# DLPG_ctrl_v3.net
KiCad netlist of a schematic drawn in EAGLE
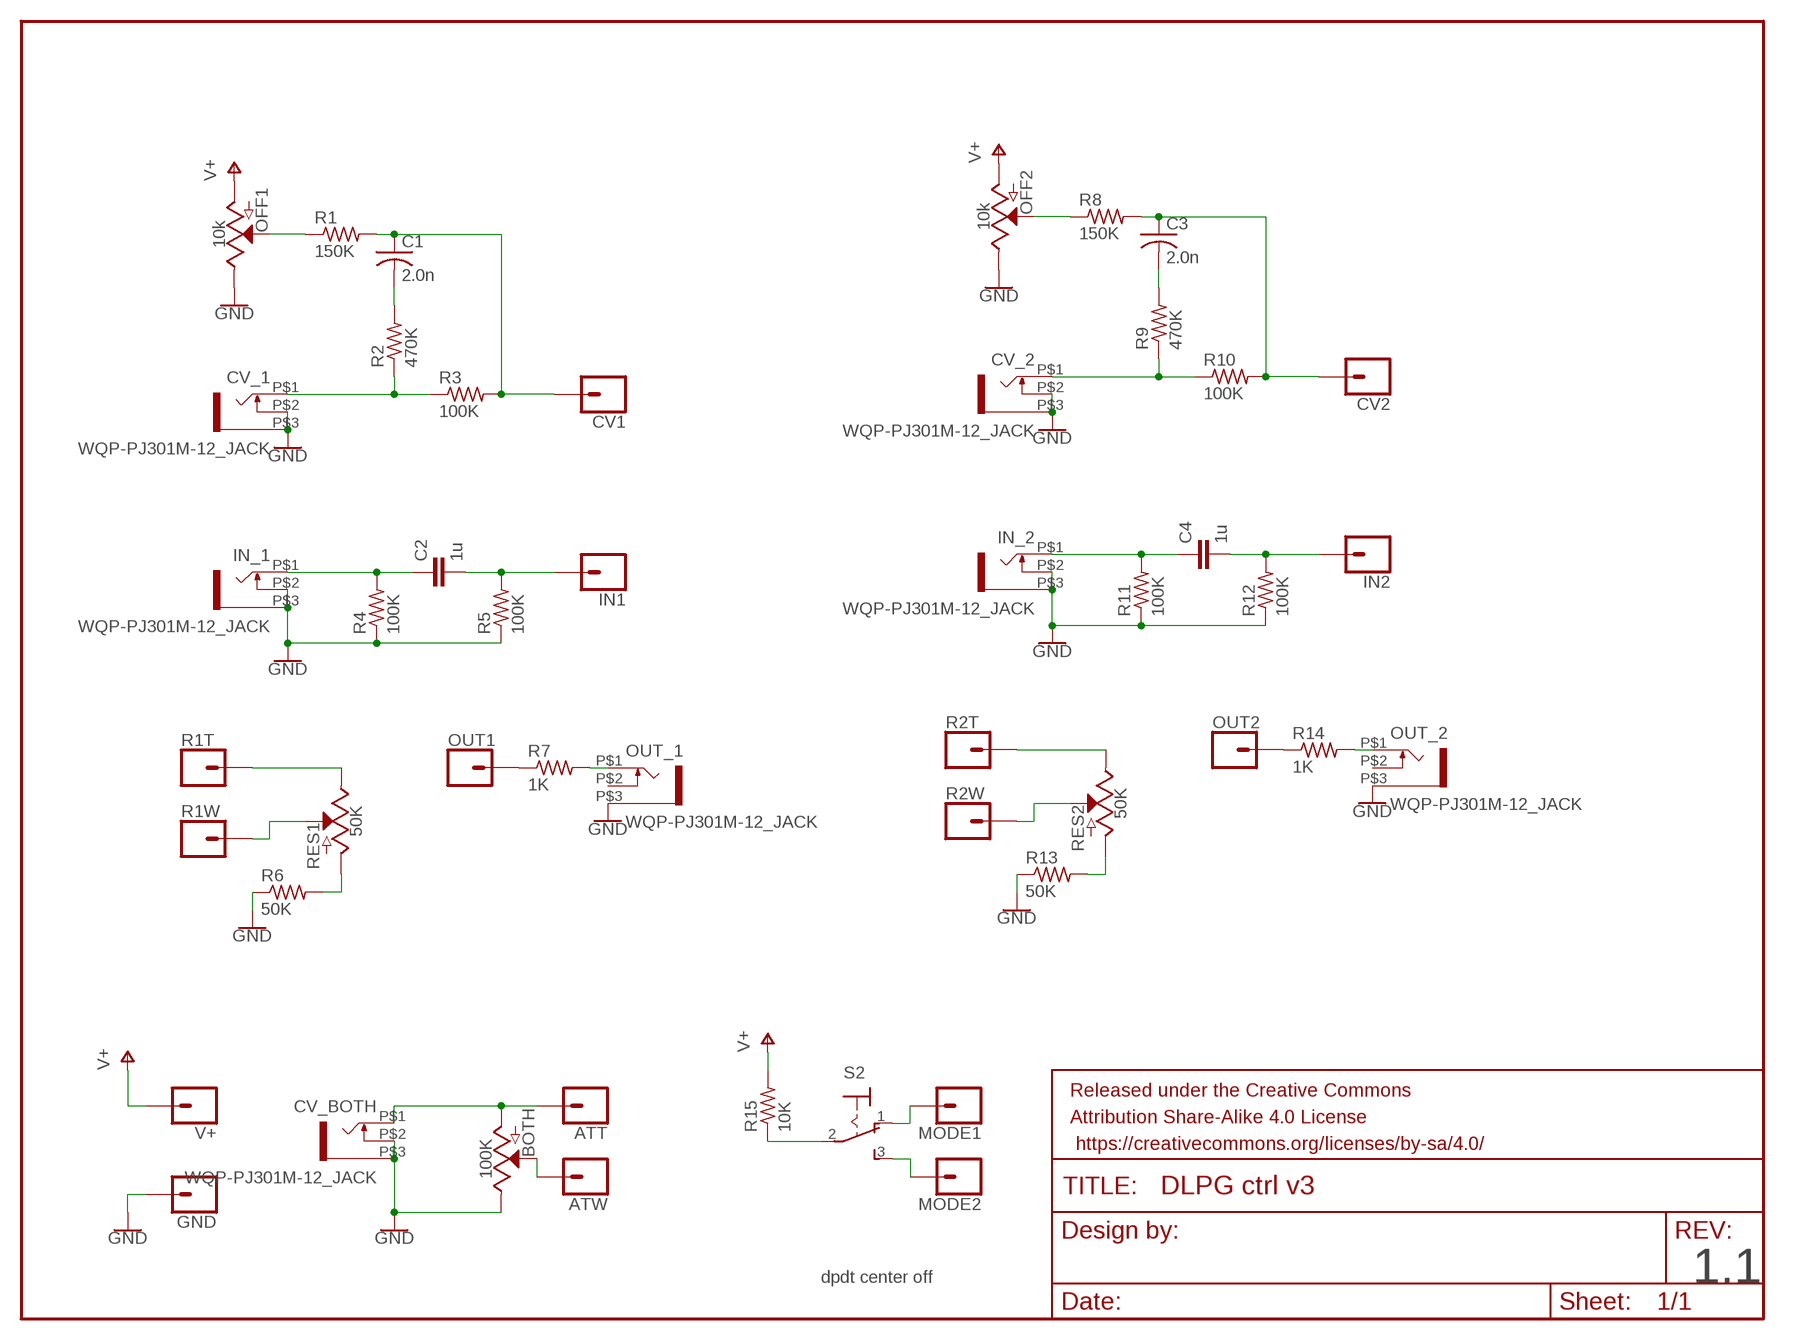
[diagram p0: schematic, sheet 1]

(export (version "E")
  (design (tool "Eeschema 10.0.6"))
  (components
    (comp (ref "ATT")
      (value "CONN_01")
      (footprint "eagle-import:1X01")
      (libsource (lib "eagle-import") (part "CONN_01"))
    )
    (comp (ref "ATW")
      (value "CONN_01")
      (footprint "eagle-import:1X01")
      (libsource (lib "eagle-import") (part "CONN_01"))
    )
    (comp (ref "BOTH")
      (value "100K")
      (footprint "eagle-import:POT-PTH-ALPS")
      (libsource (lib "eagle-import") (part "POTENTIOMETER-PTH-9MM-1/20W-20%"))
    )
    (comp (ref "C1")
      (value "2.0n")
      (footprint "eagle-import:C0805K")
      (libsource (lib "eagle-import") (part "C-USC0805K"))
    )
    (comp (ref "C2")
      (value "1u")
      (footprint "eagle-import:C2220K")
      (libsource (lib "eagle-import") (part "C-EUC2220K"))
    )
    (comp (ref "C3")
      (value "2.0n")
      (footprint "eagle-import:C0805K")
      (libsource (lib "eagle-import") (part "C-USC0805K"))
    )
    (comp (ref "C4")
      (value "1u")
      (footprint "eagle-import:C2220K")
      (libsource (lib "eagle-import") (part "C-EUC2220K"))
    )
    (comp (ref "CV1")
      (value "CONN_01")
      (footprint "eagle-import:1X01")
      (libsource (lib "eagle-import") (part "CONN_01"))
    )
    (comp (ref "CV2")
      (value "CONN_01")
      (footprint "eagle-import:1X01")
      (libsource (lib "eagle-import") (part "CONN_01"))
    )
    (comp (ref "CV_1")
      (value "WQP-PJ301M-12_JACK")
      (footprint "eagle-import:WQP-PJ301M-12_JACK")
      (libsource (lib "eagle-import") (part "WQP-PJ301M-12_JACK"))
    )
    (comp (ref "CV_2")
      (value "WQP-PJ301M-12_JACK")
      (footprint "eagle-import:WQP-PJ301M-12_JACK")
      (libsource (lib "eagle-import") (part "WQP-PJ301M-12_JACK"))
    )
    (comp (ref "CV_BOTH")
      (value "WQP-PJ301M-12_JACK")
      (footprint "eagle-import:WQP-PJ301M-12_JACK")
      (libsource (lib "eagle-import") (part "WQP-PJ301M-12_JACK"))
    )
    (comp (ref "FRAME1")
      (value "FRAME-LETTERNO_PACKAGE")
      (footprint "eagle-import:DUMMY")
      (fields (field (name "DESIGNER") "Nobody"))
      (libsource (lib "eagle-import") (part "FRAME-LETTERNO_PACKAGE"))
    )
    (comp (ref "GND")
      (value "CONN_01")
      (footprint "eagle-import:1X01")
      (libsource (lib "eagle-import") (part "CONN_01"))
    )
    (comp (ref "IN1")
      (value "CONN_01")
      (footprint "eagle-import:1X01")
      (libsource (lib "eagle-import") (part "CONN_01"))
    )
    (comp (ref "IN2")
      (value "CONN_01")
      (footprint "eagle-import:1X01")
      (libsource (lib "eagle-import") (part "CONN_01"))
    )
    (comp (ref "IN_1")
      (value "WQP-PJ301M-12_JACK")
      (footprint "eagle-import:WQP-PJ301M-12_JACK")
      (libsource (lib "eagle-import") (part "WQP-PJ301M-12_JACK"))
    )
    (comp (ref "IN_2")
      (value "WQP-PJ301M-12_JACK")
      (footprint "eagle-import:WQP-PJ301M-12_JACK")
      (libsource (lib "eagle-import") (part "WQP-PJ301M-12_JACK"))
    )
    (comp (ref "MODE1")
      (value "CONN_01")
      (footprint "eagle-import:1X01")
      (libsource (lib "eagle-import") (part "CONN_01"))
    )
    (comp (ref "MODE2")
      (value "CONN_01")
      (footprint "eagle-import:1X01")
      (libsource (lib "eagle-import") (part "CONN_01"))
    )
    (comp (ref "OFF1")
      (value "10k")
      (footprint "eagle-import:POT-PTH-ALPS")
      (libsource (lib "eagle-import") (part "POTENTIOMETER-PTH-9MM-1/20W-20%"))
    )
    (comp (ref "OFF2")
      (value "10k")
      (footprint "eagle-import:POT-PTH-ALPS")
      (libsource (lib "eagle-import") (part "POTENTIOMETER-PTH-9MM-1/20W-20%"))
    )
    (comp (ref "OUT1")
      (value "CONN_01")
      (footprint "eagle-import:1X01")
      (libsource (lib "eagle-import") (part "CONN_01"))
    )
    (comp (ref "OUT2")
      (value "CONN_01")
      (footprint "eagle-import:1X01")
      (libsource (lib "eagle-import") (part "CONN_01"))
    )
    (comp (ref "OUT_1")
      (value "WQP-PJ301M-12_JACK")
      (footprint "eagle-import:WQP-PJ301M-12_JACK")
      (libsource (lib "eagle-import") (part "WQP-PJ301M-12_JACK"))
    )
    (comp (ref "OUT_2")
      (value "WQP-PJ301M-12_JACK")
      (footprint "eagle-import:WQP-PJ301M-12_JACK")
      (libsource (lib "eagle-import") (part "WQP-PJ301M-12_JACK"))
    )
    (comp (ref "R1")
      (value "150K")
      (footprint "eagle-import:M0805")
      (libsource (lib "eagle-import") (part "R-US_M0805"))
    )
    (comp (ref "R1T")
      (value "CONN_01")
      (footprint "eagle-import:1X01")
      (libsource (lib "eagle-import") (part "CONN_01"))
    )
    (comp (ref "R1W")
      (value "CONN_01")
      (footprint "eagle-import:1X01")
      (libsource (lib "eagle-import") (part "CONN_01"))
    )
    (comp (ref "R2")
      (value "470K")
      (footprint "eagle-import:M0805")
      (libsource (lib "eagle-import") (part "R-US_M0805"))
    )
    (comp (ref "R2T")
      (value "CONN_01")
      (footprint "eagle-import:1X01")
      (libsource (lib "eagle-import") (part "CONN_01"))
    )
    (comp (ref "R2W")
      (value "CONN_01")
      (footprint "eagle-import:1X01")
      (libsource (lib "eagle-import") (part "CONN_01"))
    )
    (comp (ref "R3")
      (value "100K")
      (footprint "eagle-import:M0805")
      (libsource (lib "eagle-import") (part "R-US_M0805"))
    )
    (comp (ref "R4")
      (value "100K")
      (footprint "eagle-import:M0805")
      (libsource (lib "eagle-import") (part "R-US_M0805"))
    )
    (comp (ref "R5")
      (value "100K")
      (footprint "eagle-import:M0805")
      (libsource (lib "eagle-import") (part "R-US_M0805"))
    )
    (comp (ref "R6")
      (value "50K")
      (footprint "eagle-import:M0805")
      (libsource (lib "eagle-import") (part "R-US_M0805"))
    )
    (comp (ref "R7")
      (value "1K")
      (footprint "eagle-import:M0805")
      (libsource (lib "eagle-import") (part "R-US_M0805"))
    )
    (comp (ref "R8")
      (value "150K")
      (footprint "eagle-import:M0805")
      (libsource (lib "eagle-import") (part "R-US_M0805"))
    )
    (comp (ref "R9")
      (value "470K")
      (footprint "eagle-import:M0805")
      (libsource (lib "eagle-import") (part "R-US_M0805"))
    )
    (comp (ref "R10")
      (value "100K")
      (footprint "eagle-import:M0805")
      (libsource (lib "eagle-import") (part "R-US_M0805"))
    )
    (comp (ref "R11")
      (value "100K")
      (footprint "eagle-import:M0805")
      (libsource (lib "eagle-import") (part "R-US_M0805"))
    )
    (comp (ref "R12")
      (value "100K")
      (footprint "eagle-import:M0805")
      (libsource (lib "eagle-import") (part "R-US_M0805"))
    )
    (comp (ref "R13")
      (value "50K")
      (footprint "eagle-import:M0805")
      (libsource (lib "eagle-import") (part "R-US_M0805"))
    )
    (comp (ref "R14")
      (value "1K")
      (footprint "eagle-import:M0805")
      (libsource (lib "eagle-import") (part "R-US_M0805"))
    )
    (comp (ref "R15")
      (value "10K")
      (footprint "eagle-import:M0805")
      (libsource (lib "eagle-import") (part "R-US_M0805"))
    )
    (comp (ref "RES1")
      (value "50K")
      (footprint "eagle-import:POT-PTH-ALPS")
      (libsource (lib "eagle-import") (part "POTENTIOMETER-PTH-9MM-1/20W-20%"))
    )
    (comp (ref "RES2")
      (value "50K")
      (footprint "eagle-import:POT-PTH-ALPS")
      (libsource (lib "eagle-import") (part "POTENTIOMETER-PTH-9MM-1/20W-20%"))
    )
    (comp (ref "S2")
      (value "M9040P")
      (footprint "eagle-import:M9040P")
      (libsource (lib "eagle-import") (part "M9040P"))
    )
    (comp (ref "V+")
      (value "CONN_01")
      (footprint "eagle-import:1X01")
      (libsource (lib "eagle-import") (part "CONN_01"))
    )
  )
  (nets
    (net (code "1") (name "GND") (class "Default")
      (node (ref "BOTH") (pin "P$1") (pinfunction "E_P$1") (pintype "passive"))
      (node (ref "CV_1") (pin "P$2") (pinfunction "3_P$2") (pintype "passive"))
      (node (ref "CV_1") (pin "P$3") (pinfunction "1_P$3") (pintype "passive"))
      (node (ref "CV_2") (pin "P$2") (pinfunction "3_P$2") (pintype "passive"))
      (node (ref "CV_2") (pin "P$3") (pinfunction "1_P$3") (pintype "passive"))
      (node (ref "CV_BOTH") (pin "P$2") (pinfunction "3_P$2") (pintype "passive"))
      (node (ref "CV_BOTH") (pin "P$3") (pinfunction "1_P$3") (pintype "passive"))
      (node (ref "GND") (pin "1") (pinfunction "1_1") (pintype "passive"))
      (node (ref "IN_1") (pin "P$2") (pinfunction "3_P$2") (pintype "passive"))
      (node (ref "IN_1") (pin "P$3") (pinfunction "1_P$3") (pintype "passive"))
      (node (ref "IN_2") (pin "P$2") (pinfunction "3_P$2") (pintype "passive"))
      (node (ref "IN_2") (pin "P$3") (pinfunction "1_P$3") (pintype "passive"))
      (node (ref "OFF1") (pin "P$1") (pinfunction "E_P$1") (pintype "passive"))
      (node (ref "OFF2") (pin "P$1") (pinfunction "E_P$1") (pintype "passive"))
      (node (ref "OUT_1") (pin "P$3") (pinfunction "1_P$3") (pintype "passive"))
      (node (ref "OUT_2") (pin "P$3") (pinfunction "1_P$3") (pintype "passive"))
      (node (ref "R11") (pin "1") (pinfunction "1_1") (pintype "passive"))
      (node (ref "R12") (pin "1") (pinfunction "1_1") (pintype "passive"))
      (node (ref "R13") (pin "1") (pinfunction "1_1") (pintype "passive"))
      (node (ref "R4") (pin "1") (pinfunction "1_1") (pintype "passive"))
      (node (ref "R5") (pin "1") (pinfunction "1_1") (pintype "passive"))
      (node (ref "R6") (pin "1") (pinfunction "1_1") (pintype "passive"))
    )
    (net (code "2") (name "Net-(BOTH-A)") (class "Default")
      (node (ref "ATT") (pin "1") (pinfunction "1_1") (pintype "passive"))
      (node (ref "BOTH") (pin "P$3") (pinfunction "A_P$3") (pintype "passive"))
      (node (ref "CV_BOTH") (pin "P$1") (pinfunction "2_P$1") (pintype "passive"))
    )
    (net (code "3") (name "Net-(BOTH-S)") (class "Default")
      (node (ref "ATW") (pin "1") (pinfunction "1_1") (pintype "passive"))
      (node (ref "BOTH") (pin "P$2") (pinfunction "S_P$2") (pintype "passive"))
    )
    (net (code "4") (name "Net-(C1-Pad1)") (class "Default")
      (node (ref "C1") (pin "1") (pinfunction "1_1") (pintype "passive"))
      (node (ref "CV1") (pin "1") (pinfunction "1_1") (pintype "passive"))
      (node (ref "R1") (pin "2") (pinfunction "2_2") (pintype "passive"))
      (node (ref "R3") (pin "2") (pinfunction "2_2") (pintype "passive"))
    )
    (net (code "5") (name "Net-(C1-Pad2)") (class "Default")
      (node (ref "C1") (pin "2") (pinfunction "2_2") (pintype "passive"))
      (node (ref "R2") (pin "2") (pinfunction "2_2") (pintype "passive"))
    )
    (net (code "6") (name "Net-(C2-Pad2)") (class "Default")
      (node (ref "C2") (pin "2") (pinfunction "2_2") (pintype "passive"))
      (node (ref "IN1") (pin "1") (pinfunction "1_1") (pintype "passive"))
      (node (ref "R5") (pin "2") (pinfunction "2_2") (pintype "passive"))
    )
    (net (code "7") (name "Net-(C3-Pad1)") (class "Default")
      (node (ref "C3") (pin "1") (pinfunction "1_1") (pintype "passive"))
      (node (ref "CV2") (pin "1") (pinfunction "1_1") (pintype "passive"))
      (node (ref "R10") (pin "2") (pinfunction "2_2") (pintype "passive"))
      (node (ref "R8") (pin "2") (pinfunction "2_2") (pintype "passive"))
    )
    (net (code "8") (name "Net-(C3-Pad2)") (class "Default")
      (node (ref "C3") (pin "2") (pinfunction "2_2") (pintype "passive"))
      (node (ref "R9") (pin "2") (pinfunction "2_2") (pintype "passive"))
    )
    (net (code "9") (name "Net-(C4-Pad2)") (class "Default")
      (node (ref "C4") (pin "2") (pinfunction "2_2") (pintype "passive"))
      (node (ref "IN2") (pin "1") (pinfunction "1_1") (pintype "passive"))
      (node (ref "R12") (pin "2") (pinfunction "2_2") (pintype "passive"))
    )
    (net (code "10") (name "Net-(CV_1-2)") (class "Default")
      (node (ref "CV_1") (pin "P$1") (pinfunction "2_P$1") (pintype "passive"))
      (node (ref "R2") (pin "1") (pinfunction "1_1") (pintype "passive"))
      (node (ref "R3") (pin "1") (pinfunction "1_1") (pintype "passive"))
    )
    (net (code "11") (name "Net-(CV_2-2)") (class "Default")
      (node (ref "CV_2") (pin "P$1") (pinfunction "2_P$1") (pintype "passive"))
      (node (ref "R10") (pin "1") (pinfunction "1_1") (pintype "passive"))
      (node (ref "R9") (pin "1") (pinfunction "1_1") (pintype "passive"))
    )
    (net (code "12") (name "Net-(IN_1-2)") (class "Default")
      (node (ref "C2") (pin "1") (pinfunction "1_1") (pintype "passive"))
      (node (ref "IN_1") (pin "P$1") (pinfunction "2_P$1") (pintype "passive"))
      (node (ref "R4") (pin "2") (pinfunction "2_2") (pintype "passive"))
    )
    (net (code "13") (name "Net-(IN_2-2)") (class "Default")
      (node (ref "C4") (pin "1") (pinfunction "1_1") (pintype "passive"))
      (node (ref "IN_2") (pin "P$1") (pinfunction "2_P$1") (pintype "passive"))
      (node (ref "R11") (pin "2") (pinfunction "2_2") (pintype "passive"))
    )
    (net (code "14") (name "Net-(OFF1-S)") (class "Default")
      (node (ref "OFF1") (pin "P$2") (pinfunction "S_P$2") (pintype "passive"))
      (node (ref "R1") (pin "1") (pinfunction "1_1") (pintype "passive"))
    )
    (net (code "15") (name "Net-(OFF2-S)") (class "Default")
      (node (ref "OFF2") (pin "P$2") (pinfunction "S_P$2") (pintype "passive"))
      (node (ref "R8") (pin "1") (pinfunction "1_1") (pintype "passive"))
    )
    (net (code "16") (name "Net-(OUT1-Pad1)") (class "Default")
      (node (ref "OUT1") (pin "1") (pinfunction "1_1") (pintype "passive"))
      (node (ref "R7") (pin "1") (pinfunction "1_1") (pintype "passive"))
    )
    (net (code "17") (name "Net-(OUT2-Pad1)") (class "Default")
      (node (ref "OUT2") (pin "1") (pinfunction "1_1") (pintype "passive"))
      (node (ref "R14") (pin "1") (pinfunction "1_1") (pintype "passive"))
    )
    (net (code "18") (name "Net-(OUT_1-2)") (class "Default")
      (node (ref "OUT_1") (pin "P$1") (pinfunction "2_P$1") (pintype "passive"))
      (node (ref "R7") (pin "2") (pinfunction "2_2") (pintype "passive"))
    )
    (net (code "19") (name "Net-(OUT_2-2)") (class "Default")
      (node (ref "OUT_2") (pin "P$1") (pinfunction "2_P$1") (pintype "passive"))
      (node (ref "R14") (pin "2") (pinfunction "2_2") (pintype "passive"))
    )
    (net (code "20") (name "Net-(RES1-A)") (class "Default")
      (node (ref "R6") (pin "2") (pinfunction "2_2") (pintype "passive"))
      (node (ref "RES1") (pin "P$3") (pinfunction "A_P$3") (pintype "passive"))
    )
    (net (code "21") (name "Net-(RES1-E)") (class "Default")
      (node (ref "R1T") (pin "1") (pinfunction "1_1") (pintype "passive"))
      (node (ref "RES1") (pin "P$1") (pinfunction "E_P$1") (pintype "passive"))
    )
    (net (code "22") (name "Net-(RES1-S)") (class "Default")
      (node (ref "R1W") (pin "1") (pinfunction "1_1") (pintype "passive"))
      (node (ref "RES1") (pin "P$2") (pinfunction "S_P$2") (pintype "passive"))
    )
    (net (code "23") (name "Net-(RES2-A)") (class "Default")
      (node (ref "R13") (pin "2") (pinfunction "2_2") (pintype "passive"))
      (node (ref "RES2") (pin "P$3") (pinfunction "A_P$3") (pintype "passive"))
    )
    (net (code "24") (name "Net-(RES2-E)") (class "Default")
      (node (ref "R2T") (pin "1") (pinfunction "1_1") (pintype "passive"))
      (node (ref "RES2") (pin "P$1") (pinfunction "E_P$1") (pintype "passive"))
    )
    (net (code "25") (name "Net-(RES2-S)") (class "Default")
      (node (ref "R2W") (pin "1") (pinfunction "1_1") (pintype "passive"))
      (node (ref "RES2") (pin "P$2") (pinfunction "S_P$2") (pintype "passive"))
    )
    (net (code "26") (name "Net-(S2-O)") (class "Default")
      (node (ref "MODE1") (pin "1") (pinfunction "1_1") (pintype "passive"))
      (node (ref "S2") (pin "1") (pinfunction "O_1") (pintype "passive"))
    )
    (net (code "27") (name "Net-(S2-P)") (class "Default")
      (node (ref "R15") (pin "1") (pinfunction "1_1") (pintype "passive"))
      (node (ref "S2") (pin "2") (pinfunction "P_2") (pintype "passive"))
    )
    (net (code "28") (name "Net-(S2-S)") (class "Default")
      (node (ref "MODE2") (pin "1") (pinfunction "1_1") (pintype "passive"))
      (node (ref "S2") (pin "3") (pinfunction "S_3") (pintype "passive"))
    )
    (net (code "29") (name "V+") (class "Default")
      (node (ref "OFF1") (pin "P$3") (pinfunction "A_P$3") (pintype "passive"))
      (node (ref "OFF2") (pin "P$3") (pinfunction "A_P$3") (pintype "passive"))
      (node (ref "R15") (pin "2") (pinfunction "2_2") (pintype "passive"))
      (node (ref "V+") (pin "1") (pinfunction "1_1") (pintype "passive"))
    )
    (net (code "30") (name "unconnected-(OUT_1-3-PadP$2)") (class "Default")
      (node (ref "OUT_1") (pin "P$2") (pinfunction "3_P$2") (pintype "passive"))
    )
    (net (code "31") (name "unconnected-(OUT_2-3-PadP$2)") (class "Default")
      (node (ref "OUT_2") (pin "P$2") (pinfunction "3_P$2") (pintype "passive"))
    )
  )
)
